# esp8266.net
KiCad netlist of a schematic drawn in EAGLE
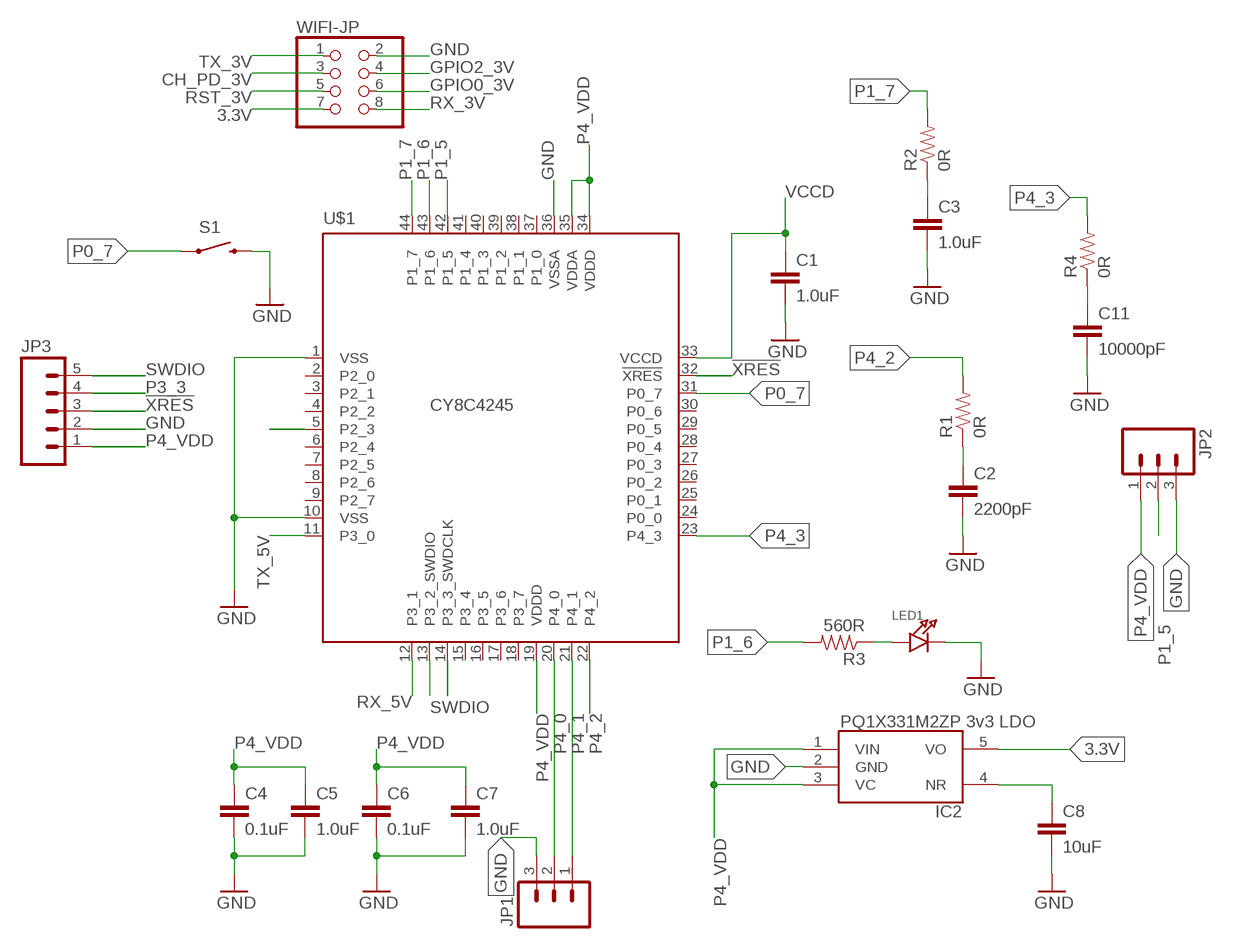
[diagram p0: schematic, sheet 1]
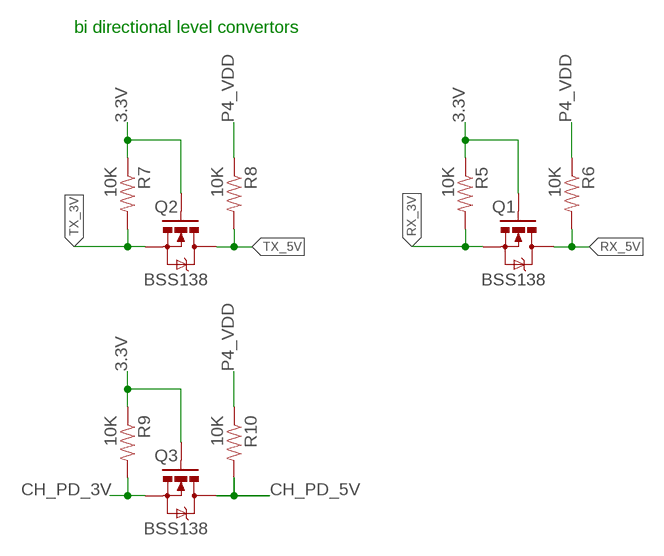
[diagram p1: schematic, sheet 2]

(export (version "E")
  (design (tool "Eeschema 10.0.6"))
  (components
    (comp (ref "C1")
      (value "1.0uF")
      (footprint "eagle-import:0805")
      (libsource (lib "eagle-import") (part "CAP0805"))
    )
    (comp (ref "C2")
      (value "2200pF")
      (footprint "eagle-import:0805")
      (libsource (lib "eagle-import") (part "CAP0805"))
    )
    (comp (ref "C3")
      (value "1.0uF")
      (footprint "eagle-import:0805")
      (libsource (lib "eagle-import") (part "CAP0805"))
    )
    (comp (ref "C4")
      (value "0.1uF")
      (footprint "eagle-import:0805")
      (libsource (lib "eagle-import") (part "CAP0805"))
    )
    (comp (ref "C5")
      (value "1.0uF")
      (footprint "eagle-import:0805")
      (libsource (lib "eagle-import") (part "CAP0805"))
    )
    (comp (ref "C6")
      (value "0.1uF")
      (footprint "eagle-import:0805")
      (libsource (lib "eagle-import") (part "CAP0805"))
    )
    (comp (ref "C7")
      (value "1.0uF")
      (footprint "eagle-import:0805")
      (libsource (lib "eagle-import") (part "CAP0805"))
    )
    (comp (ref "C8")
      (value "10uF")
      (footprint "eagle-import:0805")
      (libsource (lib "eagle-import") (part "CAP0805"))
    )
    (comp (ref "C11")
      (value "10000pF")
      (footprint "eagle-import:0805")
      (libsource (lib "eagle-import") (part "CAP0805"))
    )
    (comp (ref "IC2")
      (value "PQ1X331M2ZP-3V3-LDO-SOT-23-5")
      (footprint "eagle-import:SOT-23-5")
      (libsource (lib "eagle-import") (part "PQ1X331M2ZP-3V3-LDO-SOT-23-5"))
    )
    (comp (ref "JP1")
      (value "M031X03_NO_SILK")
      (footprint "eagle-import:1X03_NO_SILK")
      (libsource (lib "eagle-import") (part "M031X03_NO_SILK"))
    )
    (comp (ref "JP2")
      (value "M031X03_NO_SILK")
      (footprint "eagle-import:1X03_NO_SILK")
      (libsource (lib "eagle-import") (part "M031X03_NO_SILK"))
    )
    (comp (ref "JP3")
      (value "M05PTH")
      (footprint "eagle-import:1X05")
      (libsource (lib "eagle-import") (part "M05PTH"))
    )
    (comp (ref "LED1")
      (value "LED0805")
      (footprint "eagle-import:CHIPLED_0805")
      (libsource (lib "eagle-import") (part "LED0805"))
    )
    (comp (ref "R1")
      (value "0R")
      (footprint "eagle-import:0805")
      (libsource (lib "eagle-import") (part "SparkFun-Resistors_RESISTOR0805-RES"))
    )
    (comp (ref "R2")
      (value "0R")
      (footprint "eagle-import:0805")
      (libsource (lib "eagle-import") (part "SparkFun-Resistors_RESISTOR0805-RES"))
    )
    (comp (ref "R3")
      (value "560R")
      (footprint "eagle-import:0805")
      (libsource (lib "eagle-import") (part "SparkFun-Resistors_RESISTOR0805-RES"))
    )
    (comp (ref "R4")
      (value "0R")
      (footprint "eagle-import:0805")
      (libsource (lib "eagle-import") (part "SparkFun-Resistors_RESISTOR0805-RES"))
    )
    (comp (ref "S1")
      (value "SPARKFUN_SWITCH-MOMENTARY-2SMD")
      (footprint "eagle-import:SPARKFUN_TACTILE_SWITCH_SMD")
      (libsource (lib "eagle-import") (part "SPARKFUN_SWITCH-MOMENTARY-2SMD"))
    )
    (comp (ref "U$1")
      (value "CY8C4245")
      (footprint "eagle-import:TQFP44")
      (libsource (lib "eagle-import") (part "CY8C4245AXI-483"))
    )
    (comp (ref "WIFI-JP")
      (value "PINHD-2X4")
      (footprint "eagle-import:2X04")
      (libsource (lib "eagle-import") (part "PINHD-2X4"))
    )
    (comp (ref "Q1")
      (value "BSS138")
      (footprint "eagle-import:SOT23-3")
      (libsource (lib "eagle-import") (part "MOSFET-NCHANNELSMD"))
    )
    (comp (ref "Q2")
      (value "BSS138")
      (footprint "eagle-import:SOT23-3")
      (libsource (lib "eagle-import") (part "MOSFET-NCHANNELSMD"))
    )
    (comp (ref "Q3")
      (value "BSS138")
      (footprint "eagle-import:SOT23-3")
      (libsource (lib "eagle-import") (part "MOSFET-NCHANNELSMD"))
    )
    (comp (ref "R5")
      (value "10K")
      (footprint "eagle-import:0805")
      (libsource (lib "eagle-import") (part "RESISTOR0805-RES"))
    )
    (comp (ref "R6")
      (value "10K")
      (footprint "eagle-import:0805")
      (libsource (lib "eagle-import") (part "RESISTOR0805-RES"))
    )
    (comp (ref "R7")
      (value "10K")
      (footprint "eagle-import:0805")
      (libsource (lib "eagle-import") (part "RESISTOR0805-RES"))
    )
    (comp (ref "R8")
      (value "10K")
      (footprint "eagle-import:0805")
      (libsource (lib "eagle-import") (part "RESISTOR0805-RES"))
    )
    (comp (ref "R9")
      (value "10K")
      (footprint "eagle-import:0603-RES")
      (libsource (lib "eagle-import") (part "RESISTOR0603-RES"))
    )
    (comp (ref "R10")
      (value "10K")
      (footprint "eagle-import:0805")
      (libsource (lib "eagle-import") (part "RESISTOR0805-RES"))
    )
  )
  (nets
    (net (code "1") (name "3.3V") (class "Default")
      (node (ref "IC2") (pin "5") (pinfunction "VO_5") (pintype "bidirectional"))
      (node (ref "Q1") (pin "1") (pinfunction "G_1") (pintype "passive"))
      (node (ref "Q2") (pin "1") (pinfunction "G_1") (pintype "passive"))
      (node (ref "Q3") (pin "1") (pinfunction "G_1") (pintype "passive"))
      (node (ref "R5") (pin "1") (pinfunction "1_1") (pintype "passive"))
      (node (ref "R7") (pin "1") (pinfunction "1_1") (pintype "passive"))
      (node (ref "R9") (pin "1") (pinfunction "1_1") (pintype "passive"))
      (node (ref "WIFI-JP") (pin "7") (pinfunction "7_7") (pintype "passive"))
    )
    (net (code "2") (name "CH_PD_3V") (class "Default")
      (node (ref "Q3") (pin "2") (pinfunction "S_2") (pintype "passive"))
      (node (ref "R9") (pin "2") (pinfunction "2_2") (pintype "passive"))
      (node (ref "WIFI-JP") (pin "3") (pinfunction "3_3") (pintype "passive"))
    )
    (net (code "3") (name "CH_PD_5V") (class "Default")
      (node (ref "Q3") (pin "3") (pinfunction "D_3") (pintype "passive"))
      (node (ref "R10") (pin "2") (pinfunction "2_2") (pintype "passive"))
      (node (ref "U$1") (pin "5") (pinfunction "P2_3_5") (pintype "bidirectional"))
    )
    (net (code "4") (name "GND") (class "Default")
      (node (ref "C1") (pin "2") (pinfunction "2_2") (pintype "passive"))
      (node (ref "C11") (pin "2") (pinfunction "2_2") (pintype "passive"))
      (node (ref "C2") (pin "2") (pinfunction "2_2") (pintype "passive"))
      (node (ref "C3") (pin "2") (pinfunction "2_2") (pintype "passive"))
      (node (ref "C4") (pin "2") (pinfunction "2_2") (pintype "passive"))
      (node (ref "C5") (pin "2") (pinfunction "2_2") (pintype "passive"))
      (node (ref "C6") (pin "2") (pinfunction "2_2") (pintype "passive"))
      (node (ref "C7") (pin "2") (pinfunction "2_2") (pintype "passive"))
      (node (ref "C8") (pin "2") (pinfunction "2_2") (pintype "passive"))
      (node (ref "IC2") (pin "2") (pinfunction "GND_2") (pintype "bidirectional"))
      (node (ref "JP1") (pin "3") (pinfunction "3_3") (pintype "passive"))
      (node (ref "JP2") (pin "3") (pinfunction "3_3") (pintype "passive"))
      (node (ref "JP3") (pin "2") (pinfunction "2_2") (pintype "passive"))
      (node (ref "LED1") (pin "C") (pinfunction "C_C") (pintype "passive"))
      (node (ref "S1") (pin "3") (pinfunction "2_3") (pintype "passive"))
      (node (ref "U$1") (pin "1") (pinfunction "VSS_1") (pintype "power_in"))
      (node (ref "U$1") (pin "10") (pinfunction "VSS_10") (pintype "power_in"))
      (node (ref "U$1") (pin "36") (pinfunction "VSSA_36") (pintype "power_in"))
      (node (ref "WIFI-JP") (pin "2") (pinfunction "2_2") (pintype "passive"))
    )
    (net (code "5") (name "GPIO0_3V") (class "Default")
      (node (ref "WIFI-JP") (pin "6") (pinfunction "6_6") (pintype "passive"))
    )
    (net (code "6") (name "GPIO2_3V") (class "Default")
      (node (ref "WIFI-JP") (pin "4") (pinfunction "4_4") (pintype "passive"))
    )
    (net (code "7") (name "Net-(C2-Pad1)") (class "Default")
      (node (ref "C2") (pin "1") (pinfunction "1_1") (pintype "passive"))
      (node (ref "R1") (pin "1") (pinfunction "1_1") (pintype "passive"))
    )
    (net (code "8") (name "Net-(C3-Pad1)") (class "Default")
      (node (ref "C3") (pin "1") (pinfunction "1_1") (pintype "passive"))
      (node (ref "R2") (pin "1") (pinfunction "1_1") (pintype "passive"))
    )
    (net (code "9") (name "Net-(C11-Pad1)") (class "Default")
      (node (ref "C11") (pin "1") (pinfunction "1_1") (pintype "passive"))
      (node (ref "R4") (pin "1") (pinfunction "1_1") (pintype "passive"))
    )
    (net (code "10") (name "Net-(IC2-NR)") (class "Default")
      (node (ref "C8") (pin "1") (pinfunction "1_1") (pintype "passive"))
      (node (ref "IC2") (pin "4") (pinfunction "NR_4") (pintype "bidirectional"))
    )
    (net (code "11") (name "Net-(LED1-PadA)") (class "Default")
      (node (ref "LED1") (pin "A") (pinfunction "A_A") (pintype "passive"))
      (node (ref "R3") (pin "1") (pinfunction "1_1") (pintype "passive"))
    )
    (net (code "12") (name "P0_7") (class "Default")
      (node (ref "S1") (pin "1") (pinfunction "1_1") (pintype "passive"))
      (node (ref "U$1") (pin "31") (pinfunction "P0_7_31") (pintype "bidirectional"))
    )
    (net (code "13") (name "P1_5") (class "Default")
      (node (ref "JP2") (pin "2") (pinfunction "2_2") (pintype "passive"))
      (node (ref "U$1") (pin "42") (pinfunction "P1_5_42") (pintype "bidirectional"))
    )
    (net (code "14") (name "P1_6") (class "Default")
      (node (ref "R3") (pin "2") (pinfunction "2_2") (pintype "passive"))
      (node (ref "U$1") (pin "43") (pinfunction "P1_6_43") (pintype "bidirectional"))
    )
    (net (code "15") (name "P1_7") (class "Default")
      (node (ref "R2") (pin "2") (pinfunction "2_2") (pintype "passive"))
      (node (ref "U$1") (pin "44") (pinfunction "P1_7_44") (pintype "bidirectional"))
    )
    (net (code "16") (name "P3_3") (class "Default")
      (node (ref "JP3") (pin "4") (pinfunction "4_4") (pintype "passive"))
      (node (ref "U$1") (pin "14") (pinfunction "P3_3_SWDCLK_14") (pintype "bidirectional"))
    )
    (net (code "17") (name "P4_0") (class "Default")
      (node (ref "JP1") (pin "2") (pinfunction "2_2") (pintype "passive"))
      (node (ref "U$1") (pin "20") (pinfunction "P4_0_20") (pintype "bidirectional"))
    )
    (net (code "18") (name "P4_1") (class "Default")
      (node (ref "JP1") (pin "1") (pinfunction "1_1") (pintype "passive"))
      (node (ref "U$1") (pin "21") (pinfunction "P4_1_21") (pintype "bidirectional"))
    )
    (net (code "19") (name "P4_2") (class "Default")
      (node (ref "R1") (pin "2") (pinfunction "2_2") (pintype "passive"))
      (node (ref "U$1") (pin "22") (pinfunction "P4_2_22") (pintype "bidirectional"))
    )
    (net (code "20") (name "P4_3") (class "Default")
      (node (ref "R4") (pin "2") (pinfunction "2_2") (pintype "passive"))
      (node (ref "U$1") (pin "23") (pinfunction "P4_3_23") (pintype "bidirectional"))
    )
    (net (code "21") (name "P4_VDD") (class "Default")
      (node (ref "C4") (pin "1") (pinfunction "1_1") (pintype "passive"))
      (node (ref "C5") (pin "1") (pinfunction "1_1") (pintype "passive"))
      (node (ref "C6") (pin "1") (pinfunction "1_1") (pintype "passive"))
      (node (ref "C7") (pin "1") (pinfunction "1_1") (pintype "passive"))
      (node (ref "IC2") (pin "1") (pinfunction "VIN_1") (pintype "bidirectional"))
      (node (ref "IC2") (pin "3") (pinfunction "VC_3") (pintype "bidirectional"))
      (node (ref "JP2") (pin "1") (pinfunction "1_1") (pintype "passive"))
      (node (ref "JP3") (pin "1") (pinfunction "1_1") (pintype "passive"))
      (node (ref "R10") (pin "1") (pinfunction "1_1") (pintype "passive"))
      (node (ref "R6") (pin "1") (pinfunction "1_1") (pintype "passive"))
      (node (ref "R8") (pin "1") (pinfunction "1_1") (pintype "passive"))
      (node (ref "U$1") (pin "19") (pinfunction "VDDD_19") (pintype "power_in"))
      (node (ref "U$1") (pin "34") (pinfunction "VDDD_34") (pintype "power_in"))
      (node (ref "U$1") (pin "35") (pinfunction "VDDA_35") (pintype "power_in"))
    )
    (net (code "22") (name "RST_3V") (class "Default")
      (node (ref "WIFI-JP") (pin "5") (pinfunction "5_5") (pintype "passive"))
    )
    (net (code "23") (name "RX_3V") (class "Default")
      (node (ref "Q1") (pin "2") (pinfunction "S_2") (pintype "passive"))
      (node (ref "R5") (pin "2") (pinfunction "2_2") (pintype "passive"))
      (node (ref "WIFI-JP") (pin "8") (pinfunction "8_8") (pintype "passive"))
    )
    (net (code "24") (name "RX_5V") (class "Default")
      (node (ref "Q1") (pin "3") (pinfunction "D_3") (pintype "passive"))
      (node (ref "R6") (pin "2") (pinfunction "2_2") (pintype "passive"))
      (node (ref "U$1") (pin "12") (pinfunction "P3_1_12") (pintype "bidirectional"))
    )
    (net (code "25") (name "SWDIO") (class "Default")
      (node (ref "JP3") (pin "5") (pinfunction "5_5") (pintype "passive"))
      (node (ref "U$1") (pin "13") (pinfunction "P3_2_SWDIO_13") (pintype "bidirectional"))
    )
    (net (code "26") (name "TX_3V") (class "Default")
      (node (ref "Q2") (pin "2") (pinfunction "S_2") (pintype "passive"))
      (node (ref "R7") (pin "2") (pinfunction "2_2") (pintype "passive"))
      (node (ref "WIFI-JP") (pin "1") (pinfunction "1_1") (pintype "passive"))
    )
    (net (code "27") (name "TX_5V") (class "Default")
      (node (ref "Q2") (pin "3") (pinfunction "D_3") (pintype "passive"))
      (node (ref "R8") (pin "2") (pinfunction "2_2") (pintype "passive"))
      (node (ref "U$1") (pin "11") (pinfunction "P3_0_11") (pintype "bidirectional"))
    )
    (net (code "28") (name "VCCD") (class "Default")
      (node (ref "C1") (pin "1") (pinfunction "1_1") (pintype "passive"))
      (node (ref "U$1") (pin "33") (pinfunction "VCCD_33") (pintype "power_in"))
    )
    (net (code "29") (name "unconnected-(U$1-P0_0-Pad24)") (class "Default")
      (node (ref "U$1") (pin "24") (pinfunction "P0_0_24") (pintype "bidirectional"))
    )
    (net (code "30") (name "unconnected-(U$1-P0_1-Pad25)") (class "Default")
      (node (ref "U$1") (pin "25") (pinfunction "P0_1_25") (pintype "bidirectional"))
    )
    (net (code "31") (name "unconnected-(U$1-P0_2-Pad26)") (class "Default")
      (node (ref "U$1") (pin "26") (pinfunction "P0_2_26") (pintype "bidirectional"))
    )
    (net (code "32") (name "unconnected-(U$1-P0_3-Pad27)") (class "Default")
      (node (ref "U$1") (pin "27") (pinfunction "P0_3_27") (pintype "bidirectional"))
    )
    (net (code "33") (name "unconnected-(U$1-P0_4-Pad28)") (class "Default")
      (node (ref "U$1") (pin "28") (pinfunction "P0_4_28") (pintype "bidirectional"))
    )
    (net (code "34") (name "unconnected-(U$1-P0_5-Pad29)") (class "Default")
      (node (ref "U$1") (pin "29") (pinfunction "P0_5_29") (pintype "bidirectional"))
    )
    (net (code "35") (name "unconnected-(U$1-P0_6-Pad30)") (class "Default")
      (node (ref "U$1") (pin "30") (pinfunction "P0_6_30") (pintype "bidirectional"))
    )
    (net (code "36") (name "unconnected-(U$1-P1_0-Pad37)") (class "Default")
      (node (ref "U$1") (pin "37") (pinfunction "P1_0_37") (pintype "bidirectional"))
    )
    (net (code "37") (name "unconnected-(U$1-P1_1-Pad38)") (class "Default")
      (node (ref "U$1") (pin "38") (pinfunction "P1_1_38") (pintype "bidirectional"))
    )
    (net (code "38") (name "unconnected-(U$1-P1_2-Pad39)") (class "Default")
      (node (ref "U$1") (pin "39") (pinfunction "P1_2_39") (pintype "bidirectional"))
    )
    (net (code "39") (name "unconnected-(U$1-P1_3-Pad40)") (class "Default")
      (node (ref "U$1") (pin "40") (pinfunction "P1_3_40") (pintype "bidirectional"))
    )
    (net (code "40") (name "unconnected-(U$1-P1_4-Pad41)") (class "Default")
      (node (ref "U$1") (pin "41") (pinfunction "P1_4_41") (pintype "bidirectional"))
    )
    (net (code "41") (name "unconnected-(U$1-P2_0-Pad2)") (class "Default")
      (node (ref "U$1") (pin "2") (pinfunction "P2_0_2") (pintype "bidirectional"))
    )
    (net (code "42") (name "unconnected-(U$1-P2_1-Pad3)") (class "Default")
      (node (ref "U$1") (pin "3") (pinfunction "P2_1_3") (pintype "bidirectional"))
    )
    (net (code "43") (name "unconnected-(U$1-P2_2-Pad4)") (class "Default")
      (node (ref "U$1") (pin "4") (pinfunction "P2_2_4") (pintype "bidirectional"))
    )
    (net (code "44") (name "unconnected-(U$1-P2_4-Pad6)") (class "Default")
      (node (ref "U$1") (pin "6") (pinfunction "P2_4_6") (pintype "bidirectional"))
    )
    (net (code "45") (name "unconnected-(U$1-P2_5-Pad7)") (class "Default")
      (node (ref "U$1") (pin "7") (pinfunction "P2_5_7") (pintype "bidirectional"))
    )
    (net (code "46") (name "unconnected-(U$1-P2_6-Pad8)") (class "Default")
      (node (ref "U$1") (pin "8") (pinfunction "P2_6_8") (pintype "bidirectional"))
    )
    (net (code "47") (name "unconnected-(U$1-P2_7-Pad9)") (class "Default")
      (node (ref "U$1") (pin "9") (pinfunction "P2_7_9") (pintype "bidirectional"))
    )
    (net (code "48") (name "unconnected-(U$1-P3_4-Pad15)") (class "Default")
      (node (ref "U$1") (pin "15") (pinfunction "P3_4_15") (pintype "bidirectional"))
    )
    (net (code "49") (name "unconnected-(U$1-P3_5-Pad16)") (class "Default")
      (node (ref "U$1") (pin "16") (pinfunction "P3_5_16") (pintype "bidirectional"))
    )
    (net (code "50") (name "unconnected-(U$1-P3_6-Pad17)") (class "Default")
      (node (ref "U$1") (pin "17") (pinfunction "P3_6_17") (pintype "bidirectional"))
    )
    (net (code "51") (name "unconnected-(U$1-P3_7-Pad18)") (class "Default")
      (node (ref "U$1") (pin "18") (pinfunction "P3_7_18") (pintype "bidirectional"))
    )
    (net (code "52") (name "~{XRES}") (class "Default")
      (node (ref "JP3") (pin "3") (pinfunction "3_3") (pintype "passive"))
      (node (ref "U$1") (pin "32") (pinfunction "~{XRES}_32") (pintype "bidirectional"))
    )
  )
)
